# mother_board.net
KiCad netlist of a schematic drawn in EAGLE
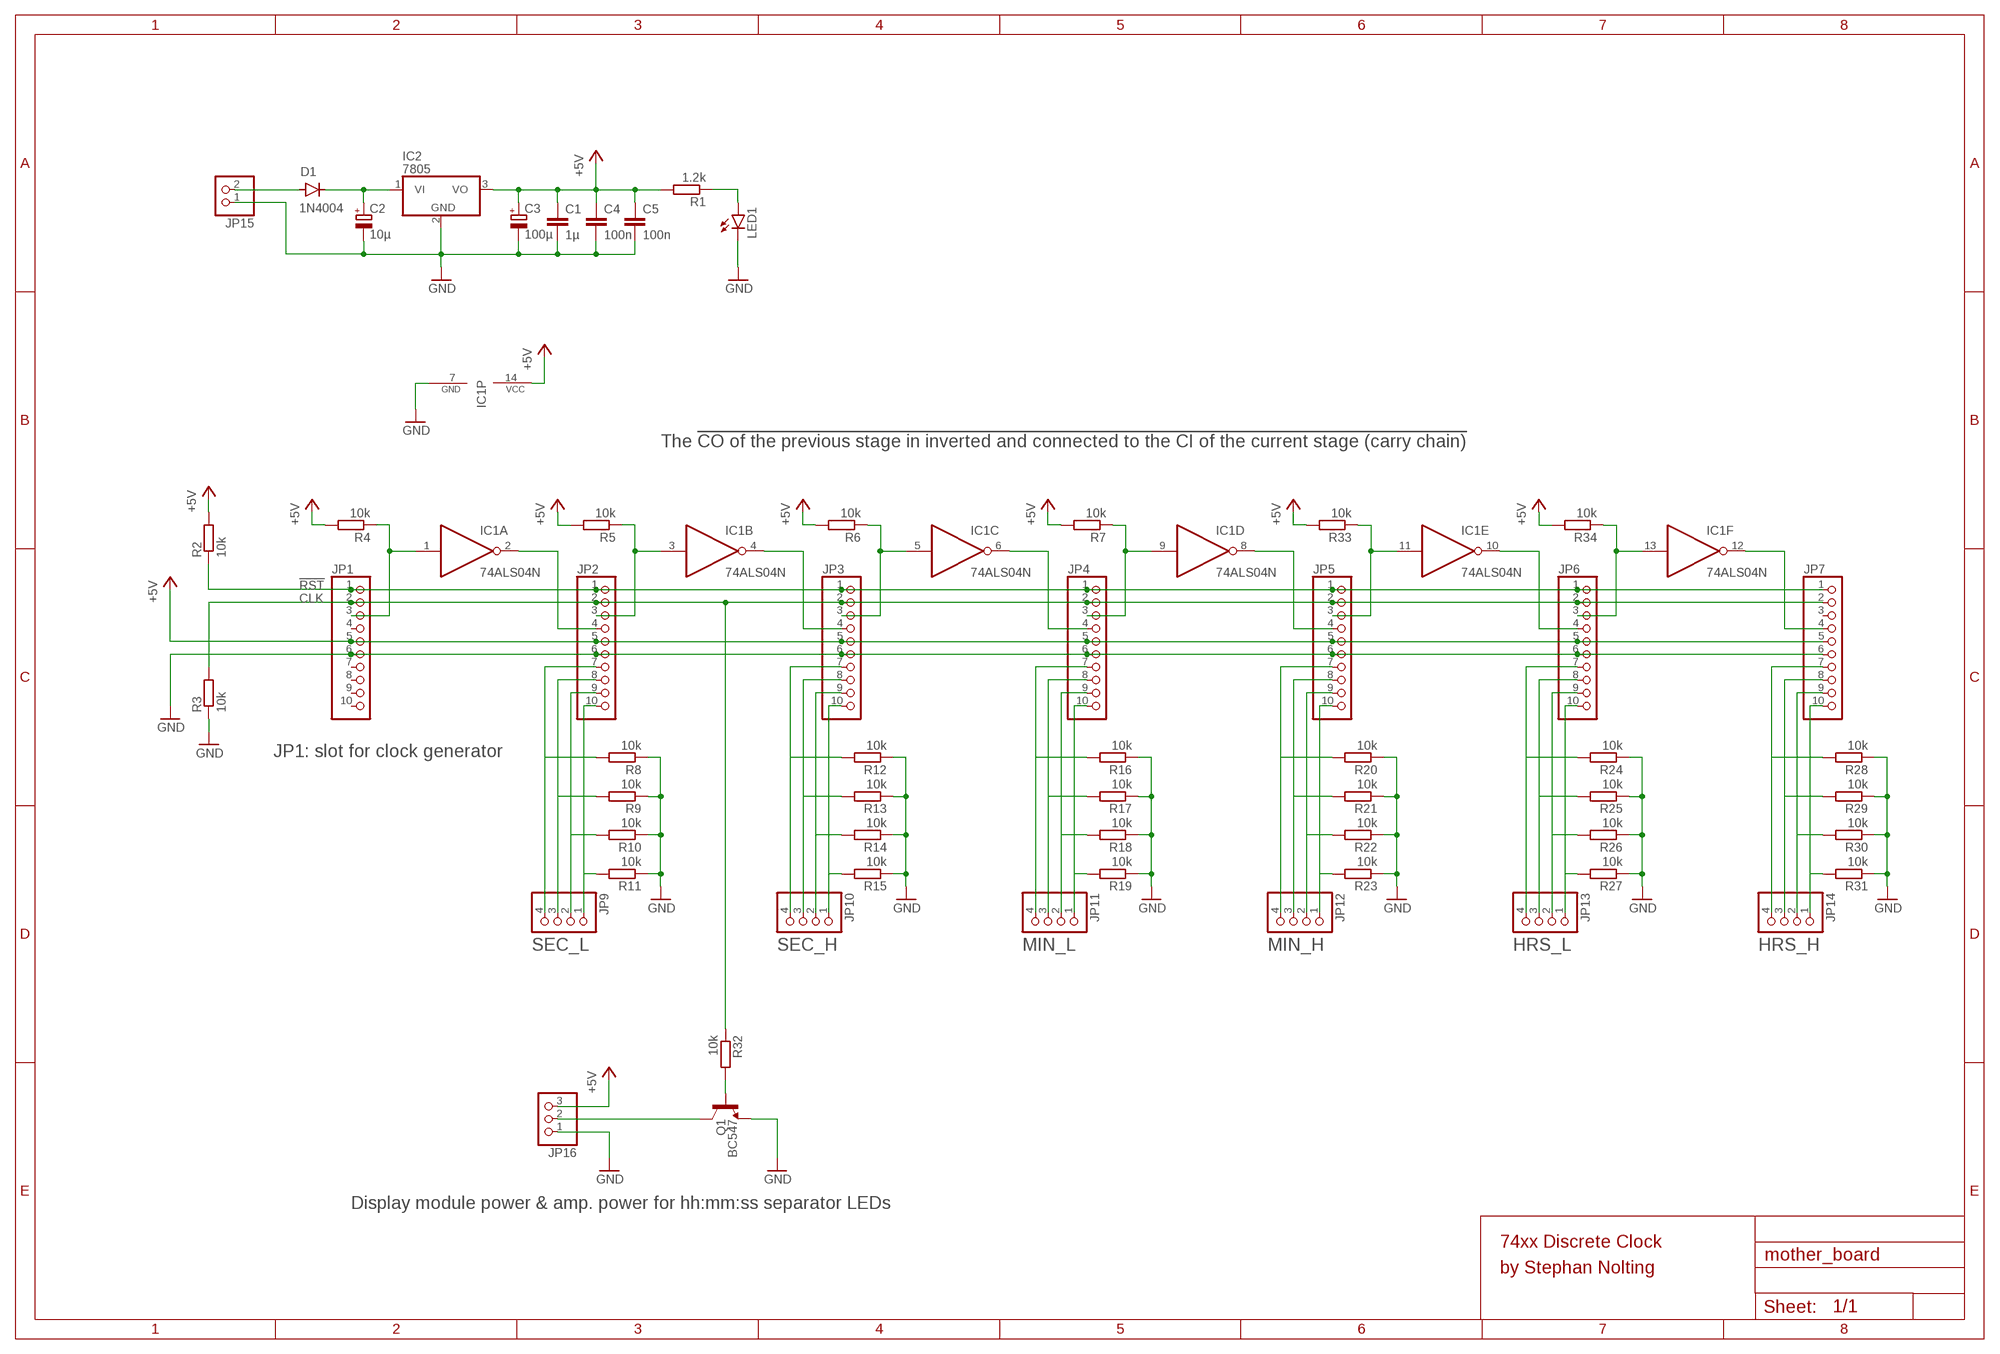
[diagram p0: schematic, sheet 1]

(export (version "E")
  (design (tool "Eeschema 10.0.6"))
  (components
    (comp (ref "C1")
      (value "1µ")
      (footprint "eagle-import:C025-024X044")
      (libsource (lib "eagle-import") (part "C-EU025-024X044"))
    )
    (comp (ref "C2")
      (value "10µ")
      (footprint "eagle-import:E2-5")
      (libsource (lib "eagle-import") (part "CPOL-EUE2-5"))
    )
    (comp (ref "C3")
      (value "100µ")
      (footprint "eagle-import:E2-5")
      (libsource (lib "eagle-import") (part "CPOL-EUE2-5"))
    )
    (comp (ref "C4")
      (value "100n")
      (footprint "eagle-import:C025-024X044")
      (libsource (lib "eagle-import") (part "C-EU025-024X044"))
    )
    (comp (ref "C5")
      (value "100n")
      (footprint "eagle-import:C025-024X044")
      (libsource (lib "eagle-import") (part "C-EU025-024X044"))
    )
    (comp (ref "D1")
      (value "1N4004")
      (footprint "eagle-import:DO-41")
      (fields
        (field (name "DIGIKEY_PART_NUMBER") "1N4004MSCT-ND")
        (field (name "MANUFACTURER") "Micro Commercial Co")
        (field (name "CREATED_BY") "PCBLayout.com")
      )
      (libsource (lib "eagle-import") (part "1N4004"))
    )
    (comp (ref "IC1")
      (value "74ALS04N")
      (footprint "eagle-import:DIL14")
      (libsource (lib "eagle-import") (part "7404NALS"))
    )
    (comp (ref "IC2")
      (value "7805")
      (footprint "eagle-import:TO220V")
      (libsource (lib "eagle-import") (part "78TV8"))
    )
    (comp (ref "JP1")
      (value "PINHD-1X10/90")
      (footprint "eagle-import:1X10_90")
      (libsource (lib "eagle-import") (part "PINHD-1X10/90"))
    )
    (comp (ref "JP2")
      (value "PINHD-1X10/90")
      (footprint "eagle-import:1X10_90")
      (libsource (lib "eagle-import") (part "PINHD-1X10/90"))
    )
    (comp (ref "JP3")
      (value "PINHD-1X10/90")
      (footprint "eagle-import:1X10_90")
      (libsource (lib "eagle-import") (part "PINHD-1X10/90"))
    )
    (comp (ref "JP4")
      (value "PINHD-1X10/90")
      (footprint "eagle-import:1X10_90")
      (libsource (lib "eagle-import") (part "PINHD-1X10/90"))
    )
    (comp (ref "JP5")
      (value "PINHD-1X10/90")
      (footprint "eagle-import:1X10_90")
      (libsource (lib "eagle-import") (part "PINHD-1X10/90"))
    )
    (comp (ref "JP6")
      (value "PINHD-1X10/90")
      (footprint "eagle-import:1X10_90")
      (libsource (lib "eagle-import") (part "PINHD-1X10/90"))
    )
    (comp (ref "JP7")
      (value "PINHD-1X10/90")
      (footprint "eagle-import:1X10_90")
      (libsource (lib "eagle-import") (part "PINHD-1X10/90"))
    )
    (comp (ref "JP9")
      (value "PINHD-1X4")
      (footprint "eagle-import:1X04")
      (libsource (lib "eagle-import") (part "PINHD-1X4"))
    )
    (comp (ref "JP10")
      (value "PINHD-1X4")
      (footprint "eagle-import:1X04")
      (libsource (lib "eagle-import") (part "PINHD-1X4"))
    )
    (comp (ref "JP11")
      (value "PINHD-1X4")
      (footprint "eagle-import:1X04")
      (libsource (lib "eagle-import") (part "PINHD-1X4"))
    )
    (comp (ref "JP12")
      (value "PINHD-1X4")
      (footprint "eagle-import:1X04")
      (libsource (lib "eagle-import") (part "PINHD-1X4"))
    )
    (comp (ref "JP13")
      (value "PINHD-1X4")
      (footprint "eagle-import:1X04")
      (libsource (lib "eagle-import") (part "PINHD-1X4"))
    )
    (comp (ref "JP14")
      (value "PINHD-1X4")
      (footprint "eagle-import:1X04")
      (libsource (lib "eagle-import") (part "PINHD-1X4"))
    )
    (comp (ref "JP15")
      (value "PINHD-1X2")
      (footprint "eagle-import:1X02")
      (libsource (lib "eagle-import") (part "PINHD-1X2"))
    )
    (comp (ref "JP16")
      (value "PINHD-1X3")
      (footprint "eagle-import:1X03")
      (libsource (lib "eagle-import") (part "PINHD-1X3"))
    )
    (comp (ref "LED1")
      (value "LED3MM")
      (footprint "eagle-import:LED3MM")
      (libsource (lib "eagle-import") (part "LED3MM"))
    )
    (comp (ref "Q1")
      (value "BC547")
      (footprint "eagle-import:TO-92")
      (libsource (lib "eagle-import") (part "TRANS_NPN-2N3904"))
    )
    (comp (ref "R1")
      (value "1.2k")
      (footprint "eagle-import:0204_7")
      (libsource (lib "eagle-import") (part "R-EU_0204/7"))
    )
    (comp (ref "R2")
      (value "10k")
      (footprint "eagle-import:0204_7")
      (libsource (lib "eagle-import") (part "R-EU_0204/7"))
    )
    (comp (ref "R3")
      (value "10k")
      (footprint "eagle-import:0204_7")
      (libsource (lib "eagle-import") (part "R-EU_0204/7"))
    )
    (comp (ref "R4")
      (value "10k")
      (footprint "eagle-import:0204_7")
      (libsource (lib "eagle-import") (part "R-EU_0204/7"))
    )
    (comp (ref "R5")
      (value "10k")
      (footprint "eagle-import:0204_7")
      (libsource (lib "eagle-import") (part "R-EU_0204/7"))
    )
    (comp (ref "R6")
      (value "10k")
      (footprint "eagle-import:0204_7")
      (libsource (lib "eagle-import") (part "R-EU_0204/7"))
    )
    (comp (ref "R7")
      (value "10k")
      (footprint "eagle-import:0204_7")
      (libsource (lib "eagle-import") (part "R-EU_0204/7"))
    )
    (comp (ref "R8")
      (value "10k")
      (footprint "eagle-import:0204_7")
      (libsource (lib "eagle-import") (part "R-EU_0204/7"))
    )
    (comp (ref "R9")
      (value "10k")
      (footprint "eagle-import:0204_7")
      (libsource (lib "eagle-import") (part "R-EU_0204/7"))
    )
    (comp (ref "R10")
      (value "10k")
      (footprint "eagle-import:0204_7")
      (libsource (lib "eagle-import") (part "R-EU_0204/7"))
    )
    (comp (ref "R11")
      (value "10k")
      (footprint "eagle-import:0204_7")
      (libsource (lib "eagle-import") (part "R-EU_0204/7"))
    )
    (comp (ref "R12")
      (value "10k")
      (footprint "eagle-import:0204_7")
      (libsource (lib "eagle-import") (part "R-EU_0204/7"))
    )
    (comp (ref "R13")
      (value "10k")
      (footprint "eagle-import:0204_7")
      (libsource (lib "eagle-import") (part "R-EU_0204/7"))
    )
    (comp (ref "R14")
      (value "10k")
      (footprint "eagle-import:0204_7")
      (libsource (lib "eagle-import") (part "R-EU_0204/7"))
    )
    (comp (ref "R15")
      (value "10k")
      (footprint "eagle-import:0204_7")
      (libsource (lib "eagle-import") (part "R-EU_0204/7"))
    )
    (comp (ref "R16")
      (value "10k")
      (footprint "eagle-import:0204_7")
      (libsource (lib "eagle-import") (part "R-EU_0204/7"))
    )
    (comp (ref "R17")
      (value "10k")
      (footprint "eagle-import:0204_7")
      (libsource (lib "eagle-import") (part "R-EU_0204/7"))
    )
    (comp (ref "R18")
      (value "10k")
      (footprint "eagle-import:0204_7")
      (libsource (lib "eagle-import") (part "R-EU_0204/7"))
    )
    (comp (ref "R19")
      (value "10k")
      (footprint "eagle-import:0204_7")
      (libsource (lib "eagle-import") (part "R-EU_0204/7"))
    )
    (comp (ref "R20")
      (value "10k")
      (footprint "eagle-import:0204_7")
      (libsource (lib "eagle-import") (part "R-EU_0204/7"))
    )
    (comp (ref "R21")
      (value "10k")
      (footprint "eagle-import:0204_7")
      (libsource (lib "eagle-import") (part "R-EU_0204/7"))
    )
    (comp (ref "R22")
      (value "10k")
      (footprint "eagle-import:0204_7")
      (libsource (lib "eagle-import") (part "R-EU_0204/7"))
    )
    (comp (ref "R23")
      (value "10k")
      (footprint "eagle-import:0204_7")
      (libsource (lib "eagle-import") (part "R-EU_0204/7"))
    )
    (comp (ref "R24")
      (value "10k")
      (footprint "eagle-import:0204_7")
      (libsource (lib "eagle-import") (part "R-EU_0204/7"))
    )
    (comp (ref "R25")
      (value "10k")
      (footprint "eagle-import:0204_7")
      (libsource (lib "eagle-import") (part "R-EU_0204/7"))
    )
    (comp (ref "R26")
      (value "10k")
      (footprint "eagle-import:0204_7")
      (libsource (lib "eagle-import") (part "R-EU_0204/7"))
    )
    (comp (ref "R27")
      (value "10k")
      (footprint "eagle-import:0204_7")
      (libsource (lib "eagle-import") (part "R-EU_0204/7"))
    )
    (comp (ref "R28")
      (value "10k")
      (footprint "eagle-import:0204_7")
      (libsource (lib "eagle-import") (part "R-EU_0204/7"))
    )
    (comp (ref "R29")
      (value "10k")
      (footprint "eagle-import:0204_7")
      (libsource (lib "eagle-import") (part "R-EU_0204/7"))
    )
    (comp (ref "R30")
      (value "10k")
      (footprint "eagle-import:0204_7")
      (libsource (lib "eagle-import") (part "R-EU_0204/7"))
    )
    (comp (ref "R31")
      (value "10k")
      (footprint "eagle-import:0204_7")
      (libsource (lib "eagle-import") (part "R-EU_0204/7"))
    )
    (comp (ref "R32")
      (value "10k")
      (footprint "eagle-import:0204_7")
      (libsource (lib "eagle-import") (part "R-EU_0204/7"))
    )
    (comp (ref "R33")
      (value "10k")
      (footprint "eagle-import:0204_7")
      (libsource (lib "eagle-import") (part "R-EU_0204/7"))
    )
    (comp (ref "R34")
      (value "10k")
      (footprint "eagle-import:0204_7")
      (libsource (lib "eagle-import") (part "R-EU_0204/7"))
    )
  )
  (nets
    (net (code "1") (name "+5V") (class "Default")
      (node (ref "C1") (pin "1") (pinfunction "1_1") (pintype "passive"))
      (node (ref "C3") (pin "+") (pinfunction "+_+") (pintype "passive"))
      (node (ref "C4") (pin "1") (pinfunction "1_1") (pintype "passive"))
      (node (ref "C5") (pin "1") (pinfunction "1_1") (pintype "passive"))
      (node (ref "IC1") (pin "14") (pinfunction "VCC_14") (pintype "power_in"))
      (node (ref "IC2") (pin "3") (pinfunction "VO_3") (pintype "passive"))
      (node (ref "JP1") (pin "5") (pinfunction "5_5") (pintype "passive"))
      (node (ref "JP16") (pin "3") (pinfunction "3_3") (pintype "passive"))
      (node (ref "JP2") (pin "5") (pinfunction "5_5") (pintype "passive"))
      (node (ref "JP3") (pin "5") (pinfunction "5_5") (pintype "passive"))
      (node (ref "JP4") (pin "5") (pinfunction "5_5") (pintype "passive"))
      (node (ref "JP5") (pin "5") (pinfunction "5_5") (pintype "passive"))
      (node (ref "JP6") (pin "5") (pinfunction "5_5") (pintype "passive"))
      (node (ref "JP7") (pin "5") (pinfunction "5_5") (pintype "passive"))
      (node (ref "R1") (pin "2") (pinfunction "2_2") (pintype "passive"))
      (node (ref "R2") (pin "2") (pinfunction "2_2") (pintype "passive"))
      (node (ref "R33") (pin "2") (pinfunction "2_2") (pintype "passive"))
      (node (ref "R34") (pin "2") (pinfunction "2_2") (pintype "passive"))
      (node (ref "R4") (pin "2") (pinfunction "2_2") (pintype "passive"))
      (node (ref "R5") (pin "2") (pinfunction "2_2") (pintype "passive"))
      (node (ref "R6") (pin "2") (pinfunction "2_2") (pintype "passive"))
      (node (ref "R7") (pin "2") (pinfunction "2_2") (pintype "passive"))
    )
    (net (code "2") (name "/CLK") (class "Default")
      (node (ref "JP1") (pin "2") (pinfunction "2_2") (pintype "passive"))
      (node (ref "JP2") (pin "2") (pinfunction "2_2") (pintype "passive"))
      (node (ref "JP3") (pin "2") (pinfunction "2_2") (pintype "passive"))
      (node (ref "JP4") (pin "2") (pinfunction "2_2") (pintype "passive"))
      (node (ref "JP5") (pin "2") (pinfunction "2_2") (pintype "passive"))
      (node (ref "JP6") (pin "2") (pinfunction "2_2") (pintype "passive"))
      (node (ref "JP7") (pin "2") (pinfunction "2_2") (pintype "passive"))
      (node (ref "R3") (pin "2") (pinfunction "2_2") (pintype "passive"))
      (node (ref "R32") (pin "1") (pinfunction "1_1") (pintype "passive"))
    )
    (net (code "3") (name "/~{RST}") (class "Default")
      (node (ref "JP1") (pin "1") (pinfunction "1_1") (pintype "passive"))
      (node (ref "JP2") (pin "1") (pinfunction "1_1") (pintype "passive"))
      (node (ref "JP3") (pin "1") (pinfunction "1_1") (pintype "passive"))
      (node (ref "JP4") (pin "1") (pinfunction "1_1") (pintype "passive"))
      (node (ref "JP5") (pin "1") (pinfunction "1_1") (pintype "passive"))
      (node (ref "JP6") (pin "1") (pinfunction "1_1") (pintype "passive"))
      (node (ref "JP7") (pin "1") (pinfunction "1_1") (pintype "passive"))
      (node (ref "R2") (pin "1") (pinfunction "1_1") (pintype "passive"))
    )
    (net (code "4") (name "GND") (class "Default")
      (node (ref "C1") (pin "2") (pinfunction "2_2") (pintype "passive"))
      (node (ref "C2") (pin "-") (pinfunction "-_-") (pintype "passive"))
      (node (ref "C3") (pin "-") (pinfunction "-_-") (pintype "passive"))
      (node (ref "C4") (pin "2") (pinfunction "2_2") (pintype "passive"))
      (node (ref "C5") (pin "2") (pinfunction "2_2") (pintype "passive"))
      (node (ref "IC1") (pin "7") (pinfunction "GND_7") (pintype "power_in"))
      (node (ref "IC2") (pin "2") (pinfunction "GND_2") (pintype "passive"))
      (node (ref "JP1") (pin "6") (pinfunction "6_6") (pintype "passive"))
      (node (ref "JP15") (pin "1") (pinfunction "1_1") (pintype "passive"))
      (node (ref "JP16") (pin "1") (pinfunction "1_1") (pintype "passive"))
      (node (ref "JP2") (pin "6") (pinfunction "6_6") (pintype "passive"))
      (node (ref "JP3") (pin "6") (pinfunction "6_6") (pintype "passive"))
      (node (ref "JP4") (pin "6") (pinfunction "6_6") (pintype "passive"))
      (node (ref "JP5") (pin "6") (pinfunction "6_6") (pintype "passive"))
      (node (ref "JP6") (pin "6") (pinfunction "6_6") (pintype "passive"))
      (node (ref "JP7") (pin "6") (pinfunction "6_6") (pintype "passive"))
      (node (ref "LED1") (pin "K") (pinfunction "C_K") (pintype "passive"))
      (node (ref "Q1") (pin "1") (pinfunction "E_1") (pintype "passive"))
      (node (ref "R10") (pin "1") (pinfunction "1_1") (pintype "passive"))
      (node (ref "R11") (pin "1") (pinfunction "1_1") (pintype "passive"))
      (node (ref "R12") (pin "1") (pinfunction "1_1") (pintype "passive"))
      (node (ref "R13") (pin "1") (pinfunction "1_1") (pintype "passive"))
      (node (ref "R14") (pin "1") (pinfunction "1_1") (pintype "passive"))
      (node (ref "R15") (pin "1") (pinfunction "1_1") (pintype "passive"))
      (node (ref "R16") (pin "1") (pinfunction "1_1") (pintype "passive"))
      (node (ref "R17") (pin "1") (pinfunction "1_1") (pintype "passive"))
      (node (ref "R18") (pin "1") (pinfunction "1_1") (pintype "passive"))
      (node (ref "R19") (pin "1") (pinfunction "1_1") (pintype "passive"))
      (node (ref "R20") (pin "1") (pinfunction "1_1") (pintype "passive"))
      (node (ref "R21") (pin "1") (pinfunction "1_1") (pintype "passive"))
      (node (ref "R22") (pin "1") (pinfunction "1_1") (pintype "passive"))
      (node (ref "R23") (pin "1") (pinfunction "1_1") (pintype "passive"))
      (node (ref "R24") (pin "1") (pinfunction "1_1") (pintype "passive"))
      (node (ref "R25") (pin "1") (pinfunction "1_1") (pintype "passive"))
      (node (ref "R26") (pin "1") (pinfunction "1_1") (pintype "passive"))
      (node (ref "R27") (pin "1") (pinfunction "1_1") (pintype "passive"))
      (node (ref "R28") (pin "1") (pinfunction "1_1") (pintype "passive"))
      (node (ref "R29") (pin "1") (pinfunction "1_1") (pintype "passive"))
      (node (ref "R3") (pin "1") (pinfunction "1_1") (pintype "passive"))
      (node (ref "R30") (pin "1") (pinfunction "1_1") (pintype "passive"))
      (node (ref "R31") (pin "1") (pinfunction "1_1") (pintype "passive"))
      (node (ref "R8") (pin "1") (pinfunction "1_1") (pintype "passive"))
      (node (ref "R9") (pin "1") (pinfunction "1_1") (pintype "passive"))
    )
    (net (code "5") (name "Net-(D1-PadA)") (class "Default")
      (node (ref "D1") (pin "A") (pinfunction "A_A") (pintype "passive"))
      (node (ref "JP15") (pin "2") (pinfunction "2_2") (pintype "passive"))
    )
    (net (code "6") (name "Net-(IC1A-I)") (class "Default")
      (node (ref "IC1") (pin "1") (pinfunction "I_1") (pintype "input"))
      (node (ref "JP1") (pin "3") (pinfunction "3_3") (pintype "passive"))
      (node (ref "R4") (pin "1") (pinfunction "1_1") (pintype "passive"))
    )
    (net (code "7") (name "Net-(IC1A-O)") (class "Default")
      (node (ref "IC1") (pin "2") (pinfunction "O_2") (pintype "output"))
      (node (ref "JP2") (pin "4") (pinfunction "4_4") (pintype "passive"))
    )
    (net (code "8") (name "Net-(IC1B-I)") (class "Default")
      (node (ref "IC1") (pin "3") (pinfunction "I_3") (pintype "input"))
      (node (ref "JP2") (pin "3") (pinfunction "3_3") (pintype "passive"))
      (node (ref "R5") (pin "1") (pinfunction "1_1") (pintype "passive"))
    )
    (net (code "9") (name "Net-(IC1B-O)") (class "Default")
      (node (ref "IC1") (pin "4") (pinfunction "O_4") (pintype "output"))
      (node (ref "JP3") (pin "4") (pinfunction "4_4") (pintype "passive"))
    )
    (net (code "10") (name "Net-(IC1C-I)") (class "Default")
      (node (ref "IC1") (pin "5") (pinfunction "I_5") (pintype "input"))
      (node (ref "JP3") (pin "3") (pinfunction "3_3") (pintype "passive"))
      (node (ref "R6") (pin "1") (pinfunction "1_1") (pintype "passive"))
    )
    (net (code "11") (name "Net-(IC1C-O)") (class "Default")
      (node (ref "IC1") (pin "6") (pinfunction "O_6") (pintype "output"))
      (node (ref "JP4") (pin "4") (pinfunction "4_4") (pintype "passive"))
    )
    (net (code "12") (name "Net-(IC1D-I)") (class "Default")
      (node (ref "IC1") (pin "9") (pinfunction "I_9") (pintype "input"))
      (node (ref "JP4") (pin "3") (pinfunction "3_3") (pintype "passive"))
      (node (ref "R7") (pin "1") (pinfunction "1_1") (pintype "passive"))
    )
    (net (code "13") (name "Net-(IC1D-O)") (class "Default")
      (node (ref "IC1") (pin "8") (pinfunction "O_8") (pintype "output"))
      (node (ref "JP5") (pin "4") (pinfunction "4_4") (pintype "passive"))
    )
    (net (code "14") (name "Net-(IC1E-I)") (class "Default")
      (node (ref "IC1") (pin "11") (pinfunction "I_11") (pintype "input"))
      (node (ref "JP5") (pin "3") (pinfunction "3_3") (pintype "passive"))
      (node (ref "R33") (pin "1") (pinfunction "1_1") (pintype "passive"))
    )
    (net (code "15") (name "Net-(IC1E-O)") (class "Default")
      (node (ref "IC1") (pin "10") (pinfunction "O_10") (pintype "output"))
      (node (ref "JP6") (pin "4") (pinfunction "4_4") (pintype "passive"))
    )
    (net (code "16") (name "Net-(IC1F-I)") (class "Default")
      (node (ref "IC1") (pin "13") (pinfunction "I_13") (pintype "input"))
      (node (ref "JP6") (pin "3") (pinfunction "3_3") (pintype "passive"))
      (node (ref "R34") (pin "1") (pinfunction "1_1") (pintype "passive"))
    )
    (net (code "17") (name "Net-(IC1F-O)") (class "Default")
      (node (ref "IC1") (pin "12") (pinfunction "O_12") (pintype "output"))
      (node (ref "JP7") (pin "4") (pinfunction "4_4") (pintype "passive"))
    )
    (net (code "18") (name "Net-(IC2-VI)") (class "Default")
      (node (ref "C2") (pin "+") (pinfunction "+_+") (pintype "passive"))
      (node (ref "D1") (pin "C") (pinfunction "C_C") (pintype "passive"))
      (node (ref "IC2") (pin "1") (pinfunction "VI_1") (pintype "input"))
    )
    (net (code "19") (name "Net-(JP2-Pad7)") (class "Default")
      (node (ref "JP2") (pin "7") (pinfunction "7_7") (pintype "passive"))
      (node (ref "JP9") (pin "4") (pinfunction "4_4") (pintype "passive"))
    )
    (net (code "20") (name "Net-(JP2-Pad8)") (class "Default")
      (node (ref "JP2") (pin "8") (pinfunction "8_8") (pintype "passive"))
      (node (ref "JP9") (pin "3") (pinfunction "3_3") (pintype "passive"))
    )
    (net (code "21") (name "Net-(JP2-Pad9)") (class "Default")
      (node (ref "JP2") (pin "9") (pinfunction "9_9") (pintype "passive"))
      (node (ref "JP9") (pin "2") (pinfunction "2_2") (pintype "passive"))
    )
    (net (code "22") (name "Net-(JP2-Pad10)") (class "Default")
      (node (ref "JP2") (pin "10") (pinfunction "10_10") (pintype "passive"))
      (node (ref "JP9") (pin "1") (pinfunction "1_1") (pintype "passive"))
    )
    (net (code "23") (name "Net-(JP10-Pad1)") (class "Default")
      (node (ref "JP10") (pin "1") (pinfunction "1_1") (pintype "passive"))
      (node (ref "JP3") (pin "10") (pinfunction "10_10") (pintype "passive"))
    )
    (net (code "24") (name "Net-(JP10-Pad2)") (class "Default")
      (node (ref "JP10") (pin "2") (pinfunction "2_2") (pintype "passive"))
      (node (ref "JP3") (pin "9") (pinfunction "9_9") (pintype "passive"))
    )
    (net (code "25") (name "Net-(JP10-Pad3)") (class "Default")
      (node (ref "JP10") (pin "3") (pinfunction "3_3") (pintype "passive"))
      (node (ref "JP3") (pin "8") (pinfunction "8_8") (pintype "passive"))
    )
    (net (code "26") (name "Net-(JP10-Pad4)") (class "Default")
      (node (ref "JP10") (pin "4") (pinfunction "4_4") (pintype "passive"))
      (node (ref "JP3") (pin "7") (pinfunction "7_7") (pintype "passive"))
    )
    (net (code "27") (name "Net-(JP11-Pad1)") (class "Default")
      (node (ref "JP11") (pin "1") (pinfunction "1_1") (pintype "passive"))
      (node (ref "JP4") (pin "10") (pinfunction "10_10") (pintype "passive"))
    )
    (net (code "28") (name "Net-(JP11-Pad2)") (class "Default")
      (node (ref "JP11") (pin "2") (pinfunction "2_2") (pintype "passive"))
      (node (ref "JP4") (pin "9") (pinfunction "9_9") (pintype "passive"))
    )
    (net (code "29") (name "Net-(JP11-Pad3)") (class "Default")
      (node (ref "JP11") (pin "3") (pinfunction "3_3") (pintype "passive"))
      (node (ref "JP4") (pin "8") (pinfunction "8_8") (pintype "passive"))
    )
    (net (code "30") (name "Net-(JP11-Pad4)") (class "Default")
      (node (ref "JP11") (pin "4") (pinfunction "4_4") (pintype "passive"))
      (node (ref "JP4") (pin "7") (pinfunction "7_7") (pintype "passive"))
    )
    (net (code "31") (name "Net-(JP12-Pad1)") (class "Default")
      (node (ref "JP12") (pin "1") (pinfunction "1_1") (pintype "passive"))
      (node (ref "JP5") (pin "10") (pinfunction "10_10") (pintype "passive"))
    )
    (net (code "32") (name "Net-(JP12-Pad2)") (class "Default")
      (node (ref "JP12") (pin "2") (pinfunction "2_2") (pintype "passive"))
      (node (ref "JP5") (pin "9") (pinfunction "9_9") (pintype "passive"))
    )
    (net (code "33") (name "Net-(JP12-Pad3)") (class "Default")
      (node (ref "JP12") (pin "3") (pinfunction "3_3") (pintype "passive"))
      (node (ref "JP5") (pin "8") (pinfunction "8_8") (pintype "passive"))
    )
    (net (code "34") (name "Net-(JP12-Pad4)") (class "Default")
      (node (ref "JP12") (pin "4") (pinfunction "4_4") (pintype "passive"))
      (node (ref "JP5") (pin "7") (pinfunction "7_7") (pintype "passive"))
    )
    (net (code "35") (name "Net-(JP13-Pad1)") (class "Default")
      (node (ref "JP13") (pin "1") (pinfunction "1_1") (pintype "passive"))
      (node (ref "JP6") (pin "10") (pinfunction "10_10") (pintype "passive"))
    )
    (net (code "36") (name "Net-(JP13-Pad2)") (class "Default")
      (node (ref "JP13") (pin "2") (pinfunction "2_2") (pintype "passive"))
      (node (ref "JP6") (pin "9") (pinfunction "9_9") (pintype "passive"))
    )
    (net (code "37") (name "Net-(JP13-Pad3)") (class "Default")
      (node (ref "JP13") (pin "3") (pinfunction "3_3") (pintype "passive"))
      (node (ref "JP6") (pin "8") (pinfunction "8_8") (pintype "passive"))
    )
    (net (code "38") (name "Net-(JP13-Pad4)") (class "Default")
      (node (ref "JP13") (pin "4") (pinfunction "4_4") (pintype "passive"))
      (node (ref "JP6") (pin "7") (pinfunction "7_7") (pintype "passive"))
    )
    (net (code "39") (name "Net-(JP14-Pad1)") (class "Default")
      (node (ref "JP14") (pin "1") (pinfunction "1_1") (pintype "passive"))
      (node (ref "JP7") (pin "10") (pinfunction "10_10") (pintype "passive"))
    )
    (net (code "40") (name "Net-(JP14-Pad2)") (class "Default")
      (node (ref "JP14") (pin "2") (pinfunction "2_2") (pintype "passive"))
      (node (ref "JP7") (pin "9") (pinfunction "9_9") (pintype "passive"))
    )
    (net (code "41") (name "Net-(JP14-Pad3)") (class "Default")
      (node (ref "JP14") (pin "3") (pinfunction "3_3") (pintype "passive"))
      (node (ref "JP7") (pin "8") (pinfunction "8_8") (pintype "passive"))
    )
    (net (code "42") (name "Net-(JP14-Pad4)") (class "Default")
      (node (ref "JP14") (pin "4") (pinfunction "4_4") (pintype "passive"))
      (node (ref "JP7") (pin "7") (pinfunction "7_7") (pintype "passive"))
    )
    (net (code "43") (name "Net-(LED1-PadA)") (class "Default")
      (node (ref "LED1") (pin "A") (pinfunction "A_A") (pintype "passive"))
      (node (ref "R1") (pin "1") (pinfunction "1_1") (pintype "passive"))
    )
    (net (code "44") (name "Net-(Q1-B)") (class "Default")
      (node (ref "Q1") (pin "2") (pinfunction "B_2") (pintype "passive"))
      (node (ref "R32") (pin "2") (pinfunction "2_2") (pintype "passive"))
    )
    (net (code "45") (name "Net-(Q1-C)") (class "Default")
      (node (ref "JP16") (pin "2") (pinfunction "2_2") (pintype "passive"))
      (node (ref "Q1") (pin "3") (pinfunction "C_3") (pintype "passive"))
    )
    (net (code "46") (name "unconnected-(JP1-Pad4)") (class "Default")
      (node (ref "JP1") (pin "4") (pinfunction "4_4") (pintype "passive"))
    )
    (net (code "47") (name "unconnected-(JP1-Pad7)") (class "Default")
      (node (ref "JP1") (pin "7") (pinfunction "7_7") (pintype "passive"))
    )
    (net (code "48") (name "unconnected-(JP1-Pad8)") (class "Default")
      (node (ref "JP1") (pin "8") (pinfunction "8_8") (pintype "passive"))
    )
    (net (code "49") (name "unconnected-(JP1-Pad9)") (class "Default")
      (node (ref "JP1") (pin "9") (pinfunction "9_9") (pintype "passive"))
    )
    (net (code "50") (name "unconnected-(JP1-Pad10)") (class "Default")
      (node (ref "JP1") (pin "10") (pinfunction "10_10") (pintype "passive"))
    )
    (net (code "51") (name "unconnected-(JP7-Pad3)") (class "Default")
      (node (ref "JP7") (pin "3") (pinfunction "3_3") (pintype "passive"))
    )
    (net (code "52") (name "unconnected-(R8-Pad2)") (class "Default")
      (node (ref "R8") (pin "2") (pinfunction "2_2") (pintype "passive"))
    )
    (net (code "53") (name "unconnected-(R9-Pad2)") (class "Default")
      (node (ref "R9") (pin "2") (pinfunction "2_2") (pintype "passive"))
    )
    (net (code "54") (name "unconnected-(R10-Pad2)") (class "Default")
      (node (ref "R10") (pin "2") (pinfunction "2_2") (pintype "passive"))
    )
    (net (code "55") (name "unconnected-(R11-Pad2)") (class "Default")
      (node (ref "R11") (pin "2") (pinfunction "2_2") (pintype "passive"))
    )
    (net (code "56") (name "unconnected-(R12-Pad2)") (class "Default")
      (node (ref "R12") (pin "2") (pinfunction "2_2") (pintype "passive"))
    )
    (net (code "57") (name "unconnected-(R13-Pad2)") (class "Default")
      (node (ref "R13") (pin "2") (pinfunction "2_2") (pintype "passive"))
    )
    (net (code "58") (name "unconnected-(R14-Pad2)") (class "Default")
      (node (ref "R14") (pin "2") (pinfunction "2_2") (pintype "passive"))
    )
    (net (code "59") (name "unconnected-(R15-Pad2)") (class "Default")
      (node (ref "R15") (pin "2") (pinfunction "2_2") (pintype "passive"))
    )
    (net (code "60") (name "unconnected-(R16-Pad2)") (class "Default")
      (node (ref "R16") (pin "2") (pinfunction "2_2") (pintype "passive"))
    )
    (net (code "61") (name "unconnected-(R17-Pad2)") (class "Default")
      (node (ref "R17") (pin "2") (pinfunction "2_2") (pintype "passive"))
    )
    (net (code "62") (name "unconnected-(R18-Pad2)") (class "Default")
      (node (ref "R18") (pin "2") (pinfunction "2_2") (pintype "passive"))
    )
    (net (code "63") (name "unconnected-(R19-Pad2)") (class "Default")
      (node (ref "R19") (pin "2") (pinfunction "2_2") (pintype "passive"))
    )
    (net (code "64") (name "unconnected-(R20-Pad2)") (class "Default")
      (node (ref "R20") (pin "2") (pinfunction "2_2") (pintype "passive"))
    )
    (net (code "65") (name "unconnected-(R21-Pad2)") (class "Default")
      (node (ref "R21") (pin "2") (pinfunction "2_2") (pintype "passive"))
    )
    (net (code "66") (name "unconnected-(R22-Pad2)") (class "Default")
      (node (ref "R22") (pin "2") (pinfunction "2_2") (pintype "passive"))
    )
    (net (code "67") (name "unconnected-(R23-Pad2)") (class "Default")
      (node (ref "R23") (pin "2") (pinfunction "2_2") (pintype "passive"))
    )
    (net (code "68") (name "unconnected-(R24-Pad2)") (class "Default")
      (node (ref "R24") (pin "2") (pinfunction "2_2") (pintype "passive"))
    )
    (net (code "69") (name "unconnected-(R25-Pad2)") (class "Default")
      (node (ref "R25") (pin "2") (pinfunction "2_2") (pintype "passive"))
    )
    (net (code "70") (name "unconnected-(R26-Pad2)") (class "Default")
      (node (ref "R26") (pin "2") (pinfunction "2_2") (pintype "passive"))
    )
    (net (code "71") (name "unconnected-(R27-Pad2)") (class "Default")
      (node (ref "R27") (pin "2") (pinfunction "2_2") (pintype "passive"))
    )
    (net (code "72") (name "unconnected-(R28-Pad2)") (class "Default")
      (node (ref "R28") (pin "2") (pinfunction "2_2") (pintype "passive"))
    )
    (net (code "73") (name "unconnected-(R29-Pad2)") (class "Default")
      (node (ref "R29") (pin "2") (pinfunction "2_2") (pintype "passive"))
    )
    (net (code "74") (name "unconnected-(R30-Pad2)") (class "Default")
      (node (ref "R30") (pin "2") (pinfunction "2_2") (pintype "passive"))
    )
    (net (code "75") (name "unconnected-(R31-Pad2)") (class "Default")
      (node (ref "R31") (pin "2") (pinfunction "2_2") (pintype "passive"))
    )
  )
)
